# NOR_Memory_Card.net
KiCad netlist of a schematic drawn in EAGLE
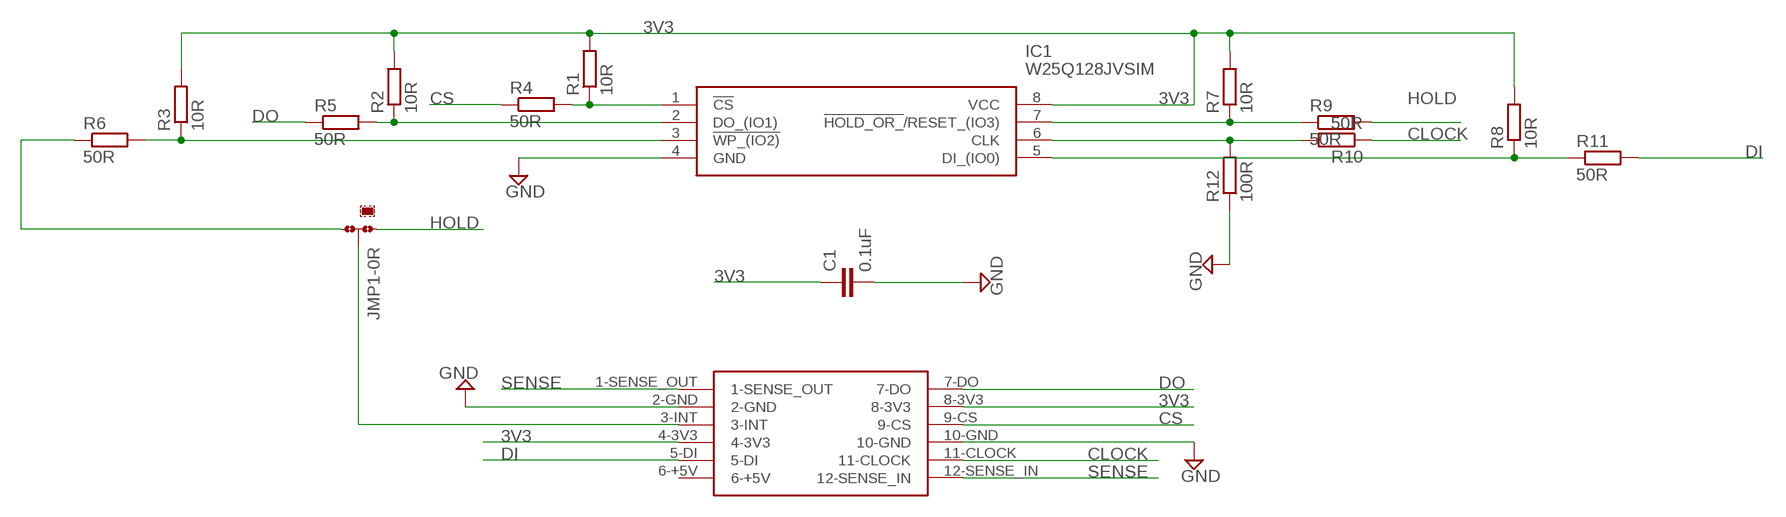
[diagram p0: schematic, sheet 1]

(export (version "E")
  (design (tool "Eeschema 10.0.6"))
  (components
    (comp (ref "C1")
      (value "0.1uF")
      (footprint "eagle-import:C0805")
      (libsource (lib "eagle-import") (part "C-EUC0805"))
    )
    (comp (ref "IC1")
      (value "W25Q128JVSIM")
      (footprint "eagle-import:SOIC127P790X216-8N")
      (fields
        (field (name "MOUSER_PART_NUMBER") "454-W25Q128JVSIM")
        (field (name "RS_PART_NUMBER") "1882648")
      )
      (libsource (lib "eagle-import") (part "W25Q128JVSIM"))
    )
    (comp (ref "JMP1")
      (value "0R-JUMPA")
      (footprint "eagle-import:A0R-JMP")
      (libsource (lib "eagle-import") (part "0R-JUMPA"))
    )
    (comp (ref "R1")
      (value "10R")
      (footprint "eagle-import:R0805")
      (libsource (lib "eagle-import") (part "R-EU_R0805"))
    )
    (comp (ref "R2")
      (value "10R")
      (footprint "eagle-import:R0805")
      (libsource (lib "eagle-import") (part "R-EU_R0805"))
    )
    (comp (ref "R3")
      (value "10R")
      (footprint "eagle-import:R0805")
      (libsource (lib "eagle-import") (part "R-EU_R0805"))
    )
    (comp (ref "R4")
      (value "50R")
      (footprint "eagle-import:R0805")
      (libsource (lib "eagle-import") (part "R-EU_R0805"))
    )
    (comp (ref "R5")
      (value "50R")
      (footprint "eagle-import:R0805")
      (libsource (lib "eagle-import") (part "R-EU_R0805"))
    )
    (comp (ref "R6")
      (value "50R")
      (footprint "eagle-import:R0805")
      (libsource (lib "eagle-import") (part "R-EU_R0805"))
    )
    (comp (ref "R7")
      (value "10R")
      (footprint "eagle-import:R0805")
      (libsource (lib "eagle-import") (part "R-EU_R0805"))
    )
    (comp (ref "R8")
      (value "10R")
      (footprint "eagle-import:R0805")
      (libsource (lib "eagle-import") (part "R-EU_R0805"))
    )
    (comp (ref "R9")
      (value "50R")
      (footprint "eagle-import:R0805")
      (libsource (lib "eagle-import") (part "R-EU_R0805"))
    )
    (comp (ref "R10")
      (value "50R")
      (footprint "eagle-import:R0805")
      (libsource (lib "eagle-import") (part "R-EU_R0805"))
    )
    (comp (ref "R11")
      (value "50R")
      (footprint "eagle-import:R0805")
      (libsource (lib "eagle-import") (part "R-EU_R0805"))
    )
    (comp (ref "R12")
      (value "100R")
      (footprint "eagle-import:R0805")
      (libsource (lib "eagle-import") (part "R-EU_R0805"))
    )
    (comp (ref "U$1")
      (value "MEM_CARD_CONN")
      (footprint "eagle-import:MEM_CARD_CONN")
      (libsource (lib "eagle-import") (part "MEM_CARD_CONN"))
    )
  )
  (nets
    (net (code "1") (name "/3V3") (class "Default")
      (node (ref "C1") (pin "1") (pinfunction "1_1") (pintype "passive"))
      (node (ref "IC1") (pin "8") (pinfunction "VCC_8") (pintype "bidirectional"))
      (node (ref "R1") (pin "2") (pinfunction "2_2") (pintype "passive"))
      (node (ref "R2") (pin "2") (pinfunction "2_2") (pintype "passive"))
      (node (ref "R3") (pin "2") (pinfunction "2_2") (pintype "passive"))
      (node (ref "R7") (pin "2") (pinfunction "2_2") (pintype "passive"))
      (node (ref "R8") (pin "2") (pinfunction "2_2") (pintype "passive"))
      (node (ref "U$1") (pin "4-3V3") (pinfunction "4-3V3_4-3V3") (pintype "power_in"))
      (node (ref "U$1") (pin "8-3V3") (pinfunction "8-3V3_8-3V3") (pintype "power_in"))
    )
    (net (code "2") (name "/CLOCK") (class "Default")
      (node (ref "R10") (pin "1") (pinfunction "1_1") (pintype "passive"))
      (node (ref "U$1") (pin "11-CLOCK") (pinfunction "11-CLOCK_11-CLOCK") (pintype "bidirectional"))
    )
    (net (code "3") (name "/CS") (class "Default")
      (node (ref "R4") (pin "1") (pinfunction "1_1") (pintype "passive"))
      (node (ref "U$1") (pin "9-CS") (pinfunction "9-CS_9-CS") (pintype "bidirectional"))
    )
    (net (code "4") (name "/DI") (class "Default")
      (node (ref "R11") (pin "2") (pinfunction "2_2") (pintype "passive"))
      (node (ref "U$1") (pin "5-DI") (pinfunction "5-DI_5-DI") (pintype "bidirectional"))
    )
    (net (code "5") (name "/DO") (class "Default")
      (node (ref "R5") (pin "1") (pinfunction "1_1") (pintype "passive"))
      (node (ref "U$1") (pin "7-DO") (pinfunction "7-DO_7-DO") (pintype "bidirectional"))
    )
    (net (code "6") (name "/HOLD") (class "Default")
      (node (ref "JMP1") (pin "1") (pinfunction "1_1") (pintype "passive"))
      (node (ref "R9") (pin "2") (pinfunction "2_2") (pintype "passive"))
    )
    (net (code "7") (name "/SENSE") (class "Default")
      (node (ref "U$1") (pin "1-SENSE_OUT") (pinfunction "1-SENSE_OUT_1-SENSE_OUT") (pintype "bidirectional"))
      (node (ref "U$1") (pin "12-SENSE_IN") (pinfunction "12-SENSE_IN_12-SENSE_IN") (pintype "bidirectional"))
    )
    (net (code "8") (name "GND") (class "Default")
      (node (ref "C1") (pin "2") (pinfunction "2_2") (pintype "passive"))
      (node (ref "IC1") (pin "4") (pinfunction "GND_4") (pintype "bidirectional"))
      (node (ref "R12") (pin "1") (pinfunction "1_1") (pintype "passive"))
      (node (ref "U$1") (pin "10-GND") (pinfunction "10-GND_10-GND") (pintype "power_in"))
      (node (ref "U$1") (pin "2-GND") (pinfunction "2-GND_2-GND") (pintype "power_in"))
    )
    (net (code "9") (name "Net-(IC1-CLK)") (class "Default")
      (node (ref "IC1") (pin "6") (pinfunction "CLK_6") (pintype "bidirectional"))
      (node (ref "R10") (pin "2") (pinfunction "2_2") (pintype "passive"))
      (node (ref "R12") (pin "2") (pinfunction "2_2") (pintype "passive"))
    )
    (net (code "10") (name "Net-(IC1-DI_(IO0))") (class "Default")
      (node (ref "IC1") (pin "5") (pinfunction "DI_(IO0)_5") (pintype "bidirectional"))
      (node (ref "R11") (pin "1") (pinfunction "1_1") (pintype "passive"))
      (node (ref "R8") (pin "1") (pinfunction "1_1") (pintype "passive"))
    )
    (net (code "11") (name "Net-(IC1-DO_(IO1))") (class "Default")
      (node (ref "IC1") (pin "2") (pinfunction "DO_(IO1)_2") (pintype "bidirectional"))
      (node (ref "R2") (pin "1") (pinfunction "1_1") (pintype "passive"))
      (node (ref "R5") (pin "2") (pinfunction "2_2") (pintype "passive"))
    )
    (net (code "12") (name "Net-(IC1-~{CS})") (class "Default")
      (node (ref "IC1") (pin "1") (pinfunction "~{CS}_1") (pintype "bidirectional"))
      (node (ref "R1") (pin "1") (pinfunction "1_1") (pintype "passive"))
      (node (ref "R4") (pin "2") (pinfunction "2_2") (pintype "passive"))
    )
    (net (code "13") (name "Net-(IC1-~{HOLD_OR_}{slash}RESET_(IO3))") (class "Default")
      (node (ref "IC1") (pin "7") (pinfunction "~{HOLD_OR_}/RESET_(IO3)_7") (pintype "bidirectional"))
      (node (ref "R7") (pin "1") (pinfunction "1_1") (pintype "passive"))
      (node (ref "R9") (pin "1") (pinfunction "1_1") (pintype "passive"))
    )
    (net (code "14") (name "Net-(IC1-~{WP_(IO2}))") (class "Default")
      (node (ref "IC1") (pin "3") (pinfunction "~{WP_(IO2})_3") (pintype "bidirectional"))
      (node (ref "R3") (pin "1") (pinfunction "1_1") (pintype "passive"))
      (node (ref "R6") (pin "2") (pinfunction "2_2") (pintype "passive"))
    )
    (net (code "15") (name "Net-(JMP1-Pad2)") (class "Default")
      (node (ref "JMP1") (pin "2") (pinfunction "2_2") (pintype "passive"))
      (node (ref "U$1") (pin "3-INT") (pinfunction "3-INT_3-INT") (pintype "bidirectional"))
    )
    (net (code "16") (name "Net-(JMP1-Pad3)") (class "Default")
      (node (ref "JMP1") (pin "3") (pinfunction "3_3") (pintype "passive"))
      (node (ref "R6") (pin "1") (pinfunction "1_1") (pintype "passive"))
    )
    (net (code "17") (name "unconnected-(U$1-Pad6-+5V)") (class "Default")
      (node (ref "U$1") (pin "6-+5V") (pinfunction "6-+5V_6-+5V") (pintype "bidirectional"))
    )
  )
)
